# ntp-alarm-clock.net
KiCad netlist of a schematic drawn in EAGLE
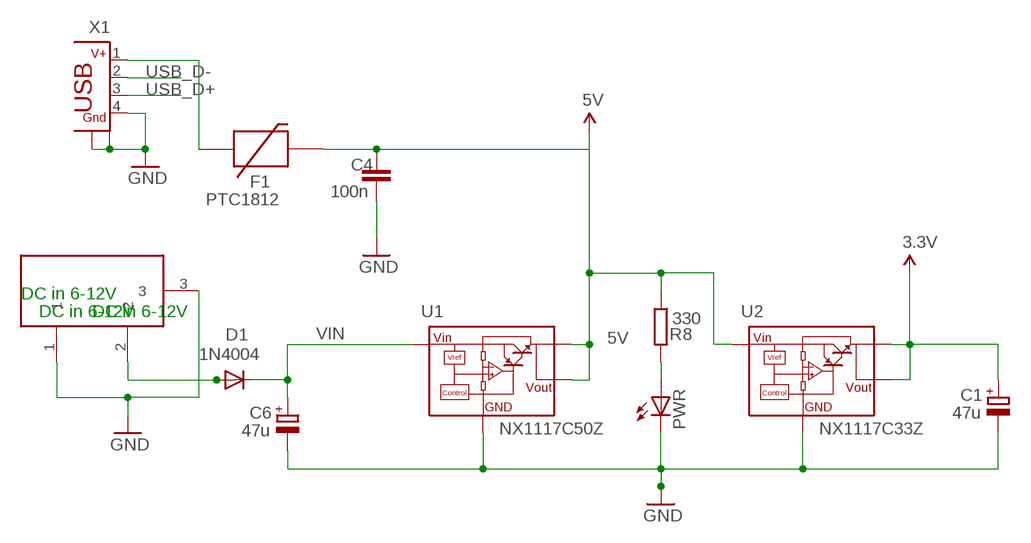
[diagram p0: schematic, sheet 1]
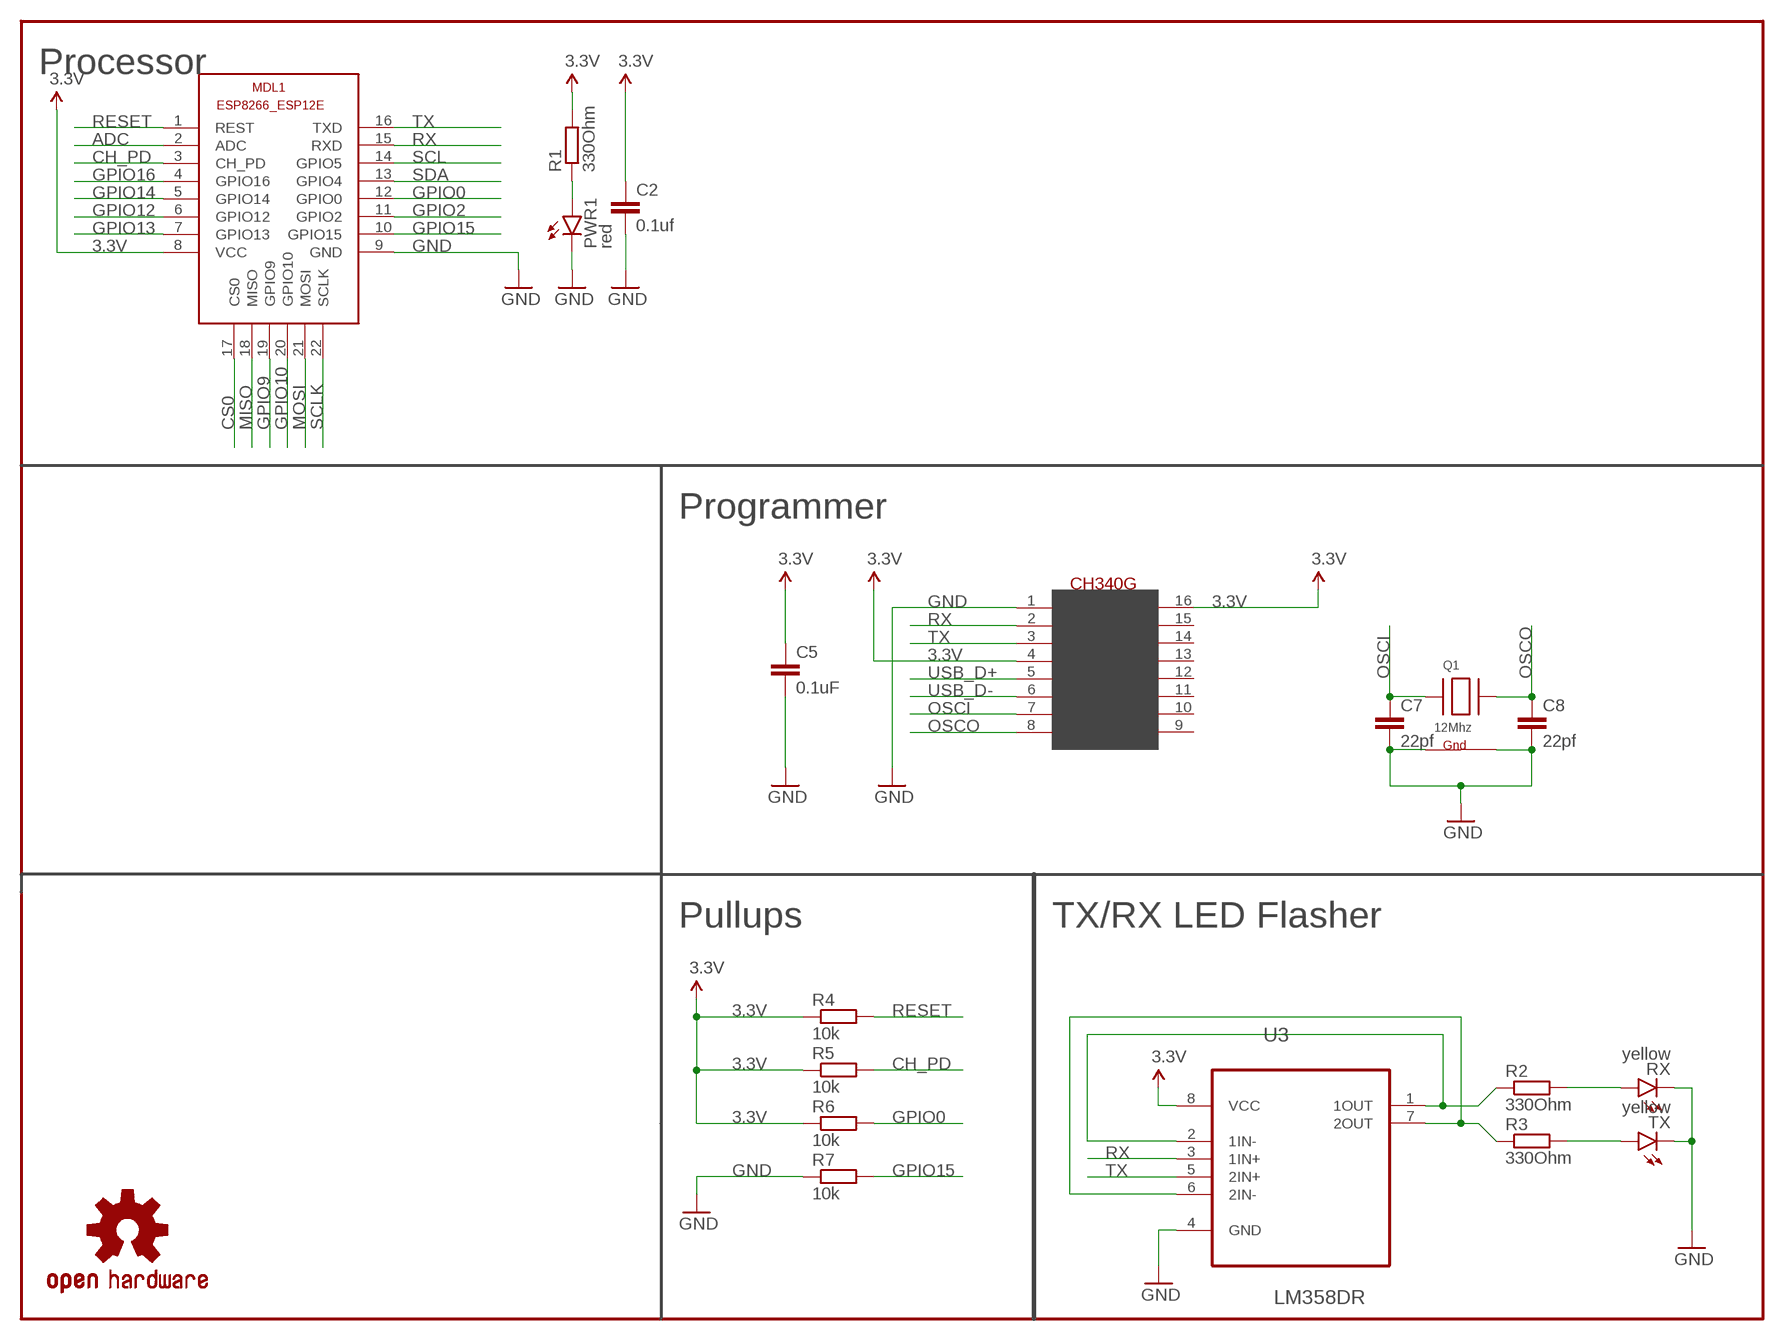
[diagram p1: schematic, sheet 2]

(export (version "E")
  (design (tool "Eeschema 10.0.6"))
  (components
    (comp (ref "C1")
      (value "47u")
      (footprint "eagle-import:PANASONIC_D")
      (libsource (lib "eagle-import") (part "CPOL-EUD"))
    )
    (comp (ref "C4")
      (value "100n")
      (footprint "eagle-import:C1206")
      (libsource (lib "eagle-import") (part "C-EUC1206"))
    )
    (comp (ref "C6")
      (value "47u")
      (footprint "eagle-import:PANASONIC_D")
      (libsource (lib "eagle-import") (part "CPOL-EUD"))
    )
    (comp (ref "D1")
      (value "1N4004")
      (footprint "eagle-import:SMA-DIODE")
      (libsource (lib "eagle-import") (part "DIODESMA"))
    )
    (comp (ref "DC1")
      (value "9V in")
      (footprint "eagle-import:DC-21MM")
      (libsource (lib "eagle-import") (part "DC21MMX"))
    )
    (comp (ref "F1")
      (value "PTC1812")
      (footprint "eagle-import:C1812")
      (libsource (lib "eagle-import") (part "PTC1812"))
    )
    (comp (ref "PWR")
      (value "LED-LCC1206")
      (footprint "eagle-import:LCC1206")
      (libsource (lib "eagle-import") (part "LED-LCC1206"))
    )
    (comp (ref "R8")
      (value "330")
      (footprint "eagle-import:R1206")
      (libsource (lib "eagle-import") (part "R-EU_R1206"))
    )
    (comp (ref "U1")
      (value "NX1117C50Z")
      (footprint "eagle-import:SOT223")
      (fields (field (name "TOLERANCE") "1.25%") (field (name "VOLTAGE") "5.0V"))
      (libsource (lib "eagle-import") (part "NX1117CZ50"))
    )
    (comp (ref "U2")
      (value "NX1117C33Z")
      (footprint "eagle-import:SOT223")
      (fields (field (name "TOLERANCE") "1.25%") (field (name "VOLTAGE") "5.0V"))
      (libsource (lib "eagle-import") (part "NX1117CZ33"))
    )
    (comp (ref "X1")
      (value "CON-USB-B")
      (footprint "eagle-import:USB-WSHIELDPADS")
      (libsource (lib "eagle-import") (part "CON-USB-B"))
    )
    (comp (ref "C2")
      (value "0.1uf")
      (footprint "eagle-import:C0805")
      (libsource (lib "eagle-import") (part "C-EUC0805"))
    )
    (comp (ref "C5")
      (value "0.1uF")
      (footprint "eagle-import:C0805")
      (libsource (lib "eagle-import") (part "C-EUC0805"))
    )
    (comp (ref "C7")
      (value "22pf")
      (footprint "eagle-import:C0805")
      (libsource (lib "eagle-import") (part "C-EUC0805"))
    )
    (comp (ref "C8")
      (value "22pf")
      (footprint "eagle-import:C0805")
      (libsource (lib "eagle-import") (part "C-EUC0805"))
    )
    (comp (ref "FRAME1")
      (value "FRAME-LETTERNO_PACKAGE")
      (footprint "eagle-import:DUMMY")
      (fields (field (name "DESIGNER") "Nobody"))
      (libsource (lib "eagle-import") (part "FRAME-LETTERNO_PACKAGE"))
    )
    (comp (ref "LOGO1")
      (value "OSHW-LOGOS")
      (footprint "eagle-import:OSHW-LOGO-S")
      (libsource (lib "eagle-import") (part "OSHW-LOGOS"))
    )
    (comp (ref "MDL1")
      (value "ESP8266-12EESP8266-ESP12E")
      (footprint "eagle-import:ESP8266-ESP12E")
      (libsource (lib "eagle-import") (part "ESP8266-12EESP8266-ESP12E"))
    )
    (comp (ref "PWR1")
      (value "red")
      (footprint "eagle-import:LED-0603")
      (libsource (lib "eagle-import") (part "LED0603"))
    )
    (comp (ref "Q1")
      (value "12Mhz")
      (footprint "eagle-import:NX3225")
      (libsource (lib "eagle-import") (part "XTAL-4-3225"))
    )
    (comp (ref "R1")
      (value "330Ohm")
      (footprint "eagle-import:R0805")
      (libsource (lib "eagle-import") (part "R-EU_R0805"))
    )
    (comp (ref "R2")
      (value "330Ohm")
      (footprint "eagle-import:R0805")
      (libsource (lib "eagle-import") (part "R-EU_R0805"))
    )
    (comp (ref "R3")
      (value "330Ohm")
      (footprint "eagle-import:R0805")
      (libsource (lib "eagle-import") (part "R-EU_R0805"))
    )
    (comp (ref "R4")
      (value "10k")
      (footprint "eagle-import:R0805")
      (libsource (lib "eagle-import") (part "R-EU_R0805"))
    )
    (comp (ref "R5")
      (value "10k")
      (footprint "eagle-import:R0805")
      (libsource (lib "eagle-import") (part "R-EU_R0805"))
    )
    (comp (ref "R6")
      (value "10k")
      (footprint "eagle-import:R0805")
      (libsource (lib "eagle-import") (part "R-EU_R0805"))
    )
    (comp (ref "R7")
      (value "10k")
      (footprint "eagle-import:R0805")
      (libsource (lib "eagle-import") (part "R-EU_R0805"))
    )
    (comp (ref "RX")
      (value "yellow")
      (footprint "eagle-import:LED-0603")
      (libsource (lib "eagle-import") (part "LED0603"))
    )
    (comp (ref "TX")
      (value "yellow")
      (footprint "eagle-import:LED-0603")
      (libsource (lib "eagle-import") (part "LED0603"))
    )
    (comp (ref "U$2")
      (value "CH340G")
      (footprint "eagle-import:SOIC16")
      (libsource (lib "eagle-import") (part "CH340G"))
    )
    (comp (ref "U3")
      (value "LM358DR")
      (footprint "eagle-import:SOIC127P600X175-8N")
      (libsource (lib "eagle-import") (part "LM358DR"))
    )
  )
  (nets
    (net (code "1") (name "3.3V") (class "Default")
      (node (ref "C1") (pin "+") (pinfunction "+_+") (pintype "passive"))
      (node (ref "C2") (pin "1") (pinfunction "1_1") (pintype "passive"))
      (node (ref "C5") (pin "1") (pinfunction "1_1") (pintype "passive"))
      (node (ref "MDL1") (pin "8") (pinfunction "VCC_8") (pintype "bidirectional"))
      (node (ref "R1") (pin "2") (pinfunction "2_2") (pintype "passive"))
      (node (ref "R4") (pin "1") (pinfunction "1_1") (pintype "passive"))
      (node (ref "R5") (pin "1") (pinfunction "1_1") (pintype "passive"))
      (node (ref "R6") (pin "1") (pinfunction "1_1") (pintype "passive"))
      (node (ref "U$2") (pin "16") (pinfunction "VCC_16") (pintype "bidirectional"))
      (node (ref "U$2") (pin "4") (pinfunction "V3_4") (pintype "bidirectional"))
      (node (ref "U2") (pin "2") (pinfunction "VOUT1_2") (pintype "output"))
      (node (ref "U2") (pin "4") (pinfunction "VOUT_4") (pintype "output"))
      (node (ref "U3") (pin "8") (pinfunction "VCC_8") (pintype "power_in"))
    )
    (net (code "2") (name "5V") (class "Default")
      (node (ref "C4") (pin "2") (pinfunction "2_2") (pintype "passive"))
      (node (ref "F1") (pin "2") (pinfunction "2_2") (pintype "bidirectional"))
      (node (ref "R8") (pin "1") (pinfunction "1_1") (pintype "passive"))
      (node (ref "U1") (pin "2") (pinfunction "VOUT1_2") (pintype "output"))
      (node (ref "U1") (pin "4") (pinfunction "VOUT_4") (pintype "output"))
      (node (ref "U2") (pin "3") (pinfunction "VIN_3") (pintype "input"))
    )
    (net (code "3") (name "ADC") (class "Default")
      (node (ref "MDL1") (pin "2") (pinfunction "ADC_2") (pintype "bidirectional"))
    )
    (net (code "4") (name "CH_PD") (class "Default")
      (node (ref "MDL1") (pin "3") (pinfunction "CH_PD_3") (pintype "bidirectional"))
      (node (ref "R5") (pin "2") (pinfunction "2_2") (pintype "passive"))
    )
    (net (code "5") (name "CS0") (class "Default")
      (node (ref "MDL1") (pin "17") (pinfunction "CS0_17") (pintype "bidirectional"))
    )
    (net (code "6") (name "GND") (class "Default")
      (node (ref "C1") (pin "-") (pinfunction "-_-") (pintype "passive"))
      (node (ref "C2") (pin "2") (pinfunction "2_2") (pintype "passive"))
      (node (ref "C4") (pin "1") (pinfunction "1_1") (pintype "passive"))
      (node (ref "C5") (pin "2") (pinfunction "2_2") (pintype "passive"))
      (node (ref "C6") (pin "-") (pinfunction "-_-") (pintype "passive"))
      (node (ref "C7") (pin "2") (pinfunction "2_2") (pintype "passive"))
      (node (ref "C8") (pin "2") (pinfunction "2_2") (pintype "passive"))
      (node (ref "DC1") (pin "1") (pinfunction "1_1") (pintype "power_in"))
      (node (ref "DC1") (pin "3") (pinfunction "3_3") (pintype "power_in"))
      (node (ref "MDL1") (pin "9") (pinfunction "GND_9") (pintype "bidirectional"))
      (node (ref "PWR") (pin "C") (pinfunction "C_C") (pintype "passive"))
      (node (ref "PWR1") (pin "C") (pinfunction "C_C") (pintype "passive"))
      (node (ref "Q1") (pin "2") (pinfunction "G2_2") (pintype "power_in"))
      (node (ref "Q1") (pin "4") (pinfunction "G1_4") (pintype "power_in"))
      (node (ref "R7") (pin "1") (pinfunction "1_1") (pintype "passive"))
      (node (ref "RX") (pin "C") (pinfunction "C_C") (pintype "passive"))
      (node (ref "TX") (pin "C") (pinfunction "C_C") (pintype "passive"))
      (node (ref "U$2") (pin "1") (pinfunction "GND_1") (pintype "bidirectional"))
      (node (ref "U1") (pin "1") (pinfunction "GND_1") (pintype "passive"))
      (node (ref "U2") (pin "1") (pinfunction "GND_1") (pintype "passive"))
      (node (ref "U3") (pin "4") (pinfunction "GND_4") (pintype "passive"))
      (node (ref "X1") (pin "4") (pinfunction "4_4") (pintype "bidirectional"))
      (node (ref "X1") (pin "SH1") (pinfunction "GND_SH1") (pintype "power_in"))
      (node (ref "X1") (pin "SH2") (pinfunction "GND_SH2") (pintype "power_in"))
    )
    (net (code "7") (name "GPIO0") (class "Default")
      (node (ref "MDL1") (pin "12") (pinfunction "GPIO0_12") (pintype "bidirectional"))
      (node (ref "R6") (pin "2") (pinfunction "2_2") (pintype "passive"))
    )
    (net (code "8") (name "GPIO2") (class "Default")
      (node (ref "MDL1") (pin "11") (pinfunction "GPIO2_11") (pintype "bidirectional"))
    )
    (net (code "9") (name "GPIO9") (class "Default")
      (node (ref "MDL1") (pin "19") (pinfunction "GPIO9_19") (pintype "bidirectional"))
    )
    (net (code "10") (name "GPIO10") (class "Default")
      (node (ref "MDL1") (pin "20") (pinfunction "GPIO10_20") (pintype "bidirectional"))
    )
    (net (code "11") (name "GPIO12") (class "Default")
      (node (ref "MDL1") (pin "6") (pinfunction "GPIO12_6") (pintype "bidirectional"))
    )
    (net (code "12") (name "GPIO13") (class "Default")
      (node (ref "MDL1") (pin "7") (pinfunction "GPIO13_7") (pintype "bidirectional"))
    )
    (net (code "13") (name "GPIO14") (class "Default")
      (node (ref "MDL1") (pin "5") (pinfunction "GPIO14_5") (pintype "bidirectional"))
    )
    (net (code "14") (name "GPIO15") (class "Default")
      (node (ref "MDL1") (pin "10") (pinfunction "GPIO15_10") (pintype "bidirectional"))
      (node (ref "R7") (pin "2") (pinfunction "2_2") (pintype "passive"))
    )
    (net (code "15") (name "GPIO16") (class "Default")
      (node (ref "MDL1") (pin "4") (pinfunction "GPIO16_4") (pintype "bidirectional"))
    )
    (net (code "16") (name "MISO") (class "Default")
      (node (ref "MDL1") (pin "18") (pinfunction "MISO_18") (pintype "bidirectional"))
    )
    (net (code "17") (name "MOSI") (class "Default")
      (node (ref "MDL1") (pin "21") (pinfunction "MOSI_21") (pintype "bidirectional"))
    )
    (net (code "18") (name "Net-(D1-PadA)") (class "Default")
      (node (ref "D1") (pin "A") (pinfunction "A_A") (pintype "passive"))
      (node (ref "DC1") (pin "2") (pinfunction "2_2") (pintype "power_in"))
    )
    (net (code "19") (name "Net-(F1-Pad1)") (class "Default")
      (node (ref "F1") (pin "1") (pinfunction "1_1") (pintype "bidirectional"))
      (node (ref "X1") (pin "1") (pinfunction "1_1") (pintype "bidirectional"))
    )
    (net (code "20") (name "Net-(PWR-PadA)") (class "Default")
      (node (ref "PWR") (pin "A") (pinfunction "A_A") (pintype "passive"))
      (node (ref "R8") (pin "2") (pinfunction "2_2") (pintype "passive"))
    )
    (net (code "21") (name "Net-(PWR1-PadA)") (class "Default")
      (node (ref "PWR1") (pin "A") (pinfunction "A_A") (pintype "passive"))
      (node (ref "R1") (pin "1") (pinfunction "1_1") (pintype "passive"))
    )
    (net (code "22") (name "Net-(R2-Pad2)") (class "Default")
      (node (ref "R2") (pin "2") (pinfunction "2_2") (pintype "passive"))
      (node (ref "RX") (pin "A") (pinfunction "A_A") (pintype "passive"))
    )
    (net (code "23") (name "Net-(R3-Pad2)") (class "Default")
      (node (ref "R3") (pin "2") (pinfunction "2_2") (pintype "passive"))
      (node (ref "TX") (pin "A") (pinfunction "A_A") (pintype "passive"))
    )
    (net (code "24") (name "Net-(U3-1IN-)") (class "Default")
      (node (ref "R2") (pin "1") (pinfunction "1_1") (pintype "passive"))
      (node (ref "U3") (pin "1") (pinfunction "1OUT_1") (pintype "output"))
      (node (ref "U3") (pin "2") (pinfunction "1IN-_2") (pintype "input"))
    )
    (net (code "25") (name "Net-(U3-2IN-)") (class "Default")
      (node (ref "R3") (pin "1") (pinfunction "1_1") (pintype "passive"))
      (node (ref "U3") (pin "6") (pinfunction "2IN-_6") (pintype "input"))
      (node (ref "U3") (pin "7") (pinfunction "2OUT_7") (pintype "output"))
    )
    (net (code "26") (name "OSCI") (class "Default")
      (node (ref "C7") (pin "1") (pinfunction "1_1") (pintype "passive"))
      (node (ref "Q1") (pin "1") (pinfunction "X1_1") (pintype "bidirectional"))
      (node (ref "U$2") (pin "7") (pinfunction "XI_7") (pintype "bidirectional"))
    )
    (net (code "27") (name "OSCO") (class "Default")
      (node (ref "C8") (pin "1") (pinfunction "1_1") (pintype "passive"))
      (node (ref "Q1") (pin "3") (pinfunction "X2_3") (pintype "bidirectional"))
      (node (ref "U$2") (pin "8") (pinfunction "XO_8") (pintype "bidirectional"))
    )
    (net (code "28") (name "RESET") (class "Default")
      (node (ref "MDL1") (pin "1") (pinfunction "REST_1") (pintype "bidirectional"))
      (node (ref "R4") (pin "2") (pinfunction "2_2") (pintype "passive"))
    )
    (net (code "29") (name "RX") (class "Default")
      (node (ref "MDL1") (pin "15") (pinfunction "RXD_15") (pintype "bidirectional"))
      (node (ref "U$2") (pin "2") (pinfunction "TX_2") (pintype "bidirectional"))
      (node (ref "U3") (pin "3") (pinfunction "1IN+_3") (pintype "input"))
    )
    (net (code "30") (name "SCL") (class "Default")
      (node (ref "MDL1") (pin "14") (pinfunction "GPIO5_14") (pintype "bidirectional"))
    )
    (net (code "31") (name "SCLK") (class "Default")
      (node (ref "MDL1") (pin "22") (pinfunction "SCLK_22") (pintype "bidirectional"))
    )
    (net (code "32") (name "SDA") (class "Default")
      (node (ref "MDL1") (pin "13") (pinfunction "GPIO4_13") (pintype "bidirectional"))
    )
    (net (code "33") (name "TX") (class "Default")
      (node (ref "MDL1") (pin "16") (pinfunction "TXD_16") (pintype "bidirectional"))
      (node (ref "U$2") (pin "3") (pinfunction "RX_3") (pintype "bidirectional"))
      (node (ref "U3") (pin "5") (pinfunction "2IN+_5") (pintype "input"))
    )
    (net (code "34") (name "USB_D+") (class "Default")
      (node (ref "U$2") (pin "5") (pinfunction "D+_5") (pintype "bidirectional"))
      (node (ref "X1") (pin "3") (pinfunction "3_3") (pintype "bidirectional"))
    )
    (net (code "35") (name "USB_D-") (class "Default")
      (node (ref "U$2") (pin "6") (pinfunction "D-_6") (pintype "bidirectional"))
      (node (ref "X1") (pin "2") (pinfunction "2_2") (pintype "bidirectional"))
    )
    (net (code "36") (name "VIN") (class "Default")
      (node (ref "C6") (pin "+") (pinfunction "+_+") (pintype "passive"))
      (node (ref "D1") (pin "C") (pinfunction "C_C") (pintype "passive"))
      (node (ref "U1") (pin "3") (pinfunction "VIN_3") (pintype "input"))
    )
    (net (code "37") (name "unconnected-(U$2-CTS-Pad9)") (class "Default")
      (node (ref "U$2") (pin "9") (pinfunction "CTS_9") (pintype "bidirectional"))
    )
    (net (code "38") (name "unconnected-(U$2-DCD-Pad12)") (class "Default")
      (node (ref "U$2") (pin "12") (pinfunction "DCD_12") (pintype "bidirectional"))
    )
    (net (code "39") (name "unconnected-(U$2-DSR-Pad10)") (class "Default")
      (node (ref "U$2") (pin "10") (pinfunction "DSR_10") (pintype "bidirectional"))
    )
    (net (code "40") (name "unconnected-(U$2-DTR-Pad13)") (class "Default")
      (node (ref "U$2") (pin "13") (pinfunction "DTR_13") (pintype "bidirectional"))
    )
    (net (code "41") (name "unconnected-(U$2-RI-Pad11)") (class "Default")
      (node (ref "U$2") (pin "11") (pinfunction "RI_11") (pintype "bidirectional"))
    )
    (net (code "42") (name "unconnected-(U$2-RS232-Pad15)") (class "Default")
      (node (ref "U$2") (pin "15") (pinfunction "RS232_15") (pintype "bidirectional"))
    )
    (net (code "43") (name "unconnected-(U$2-RTS-Pad14)") (class "Default")
      (node (ref "U$2") (pin "14") (pinfunction "RTS_14") (pintype "bidirectional"))
    )
  )
)
